# hanger0515.net
KiCad netlist of a schematic drawn in EasyEDA Pro
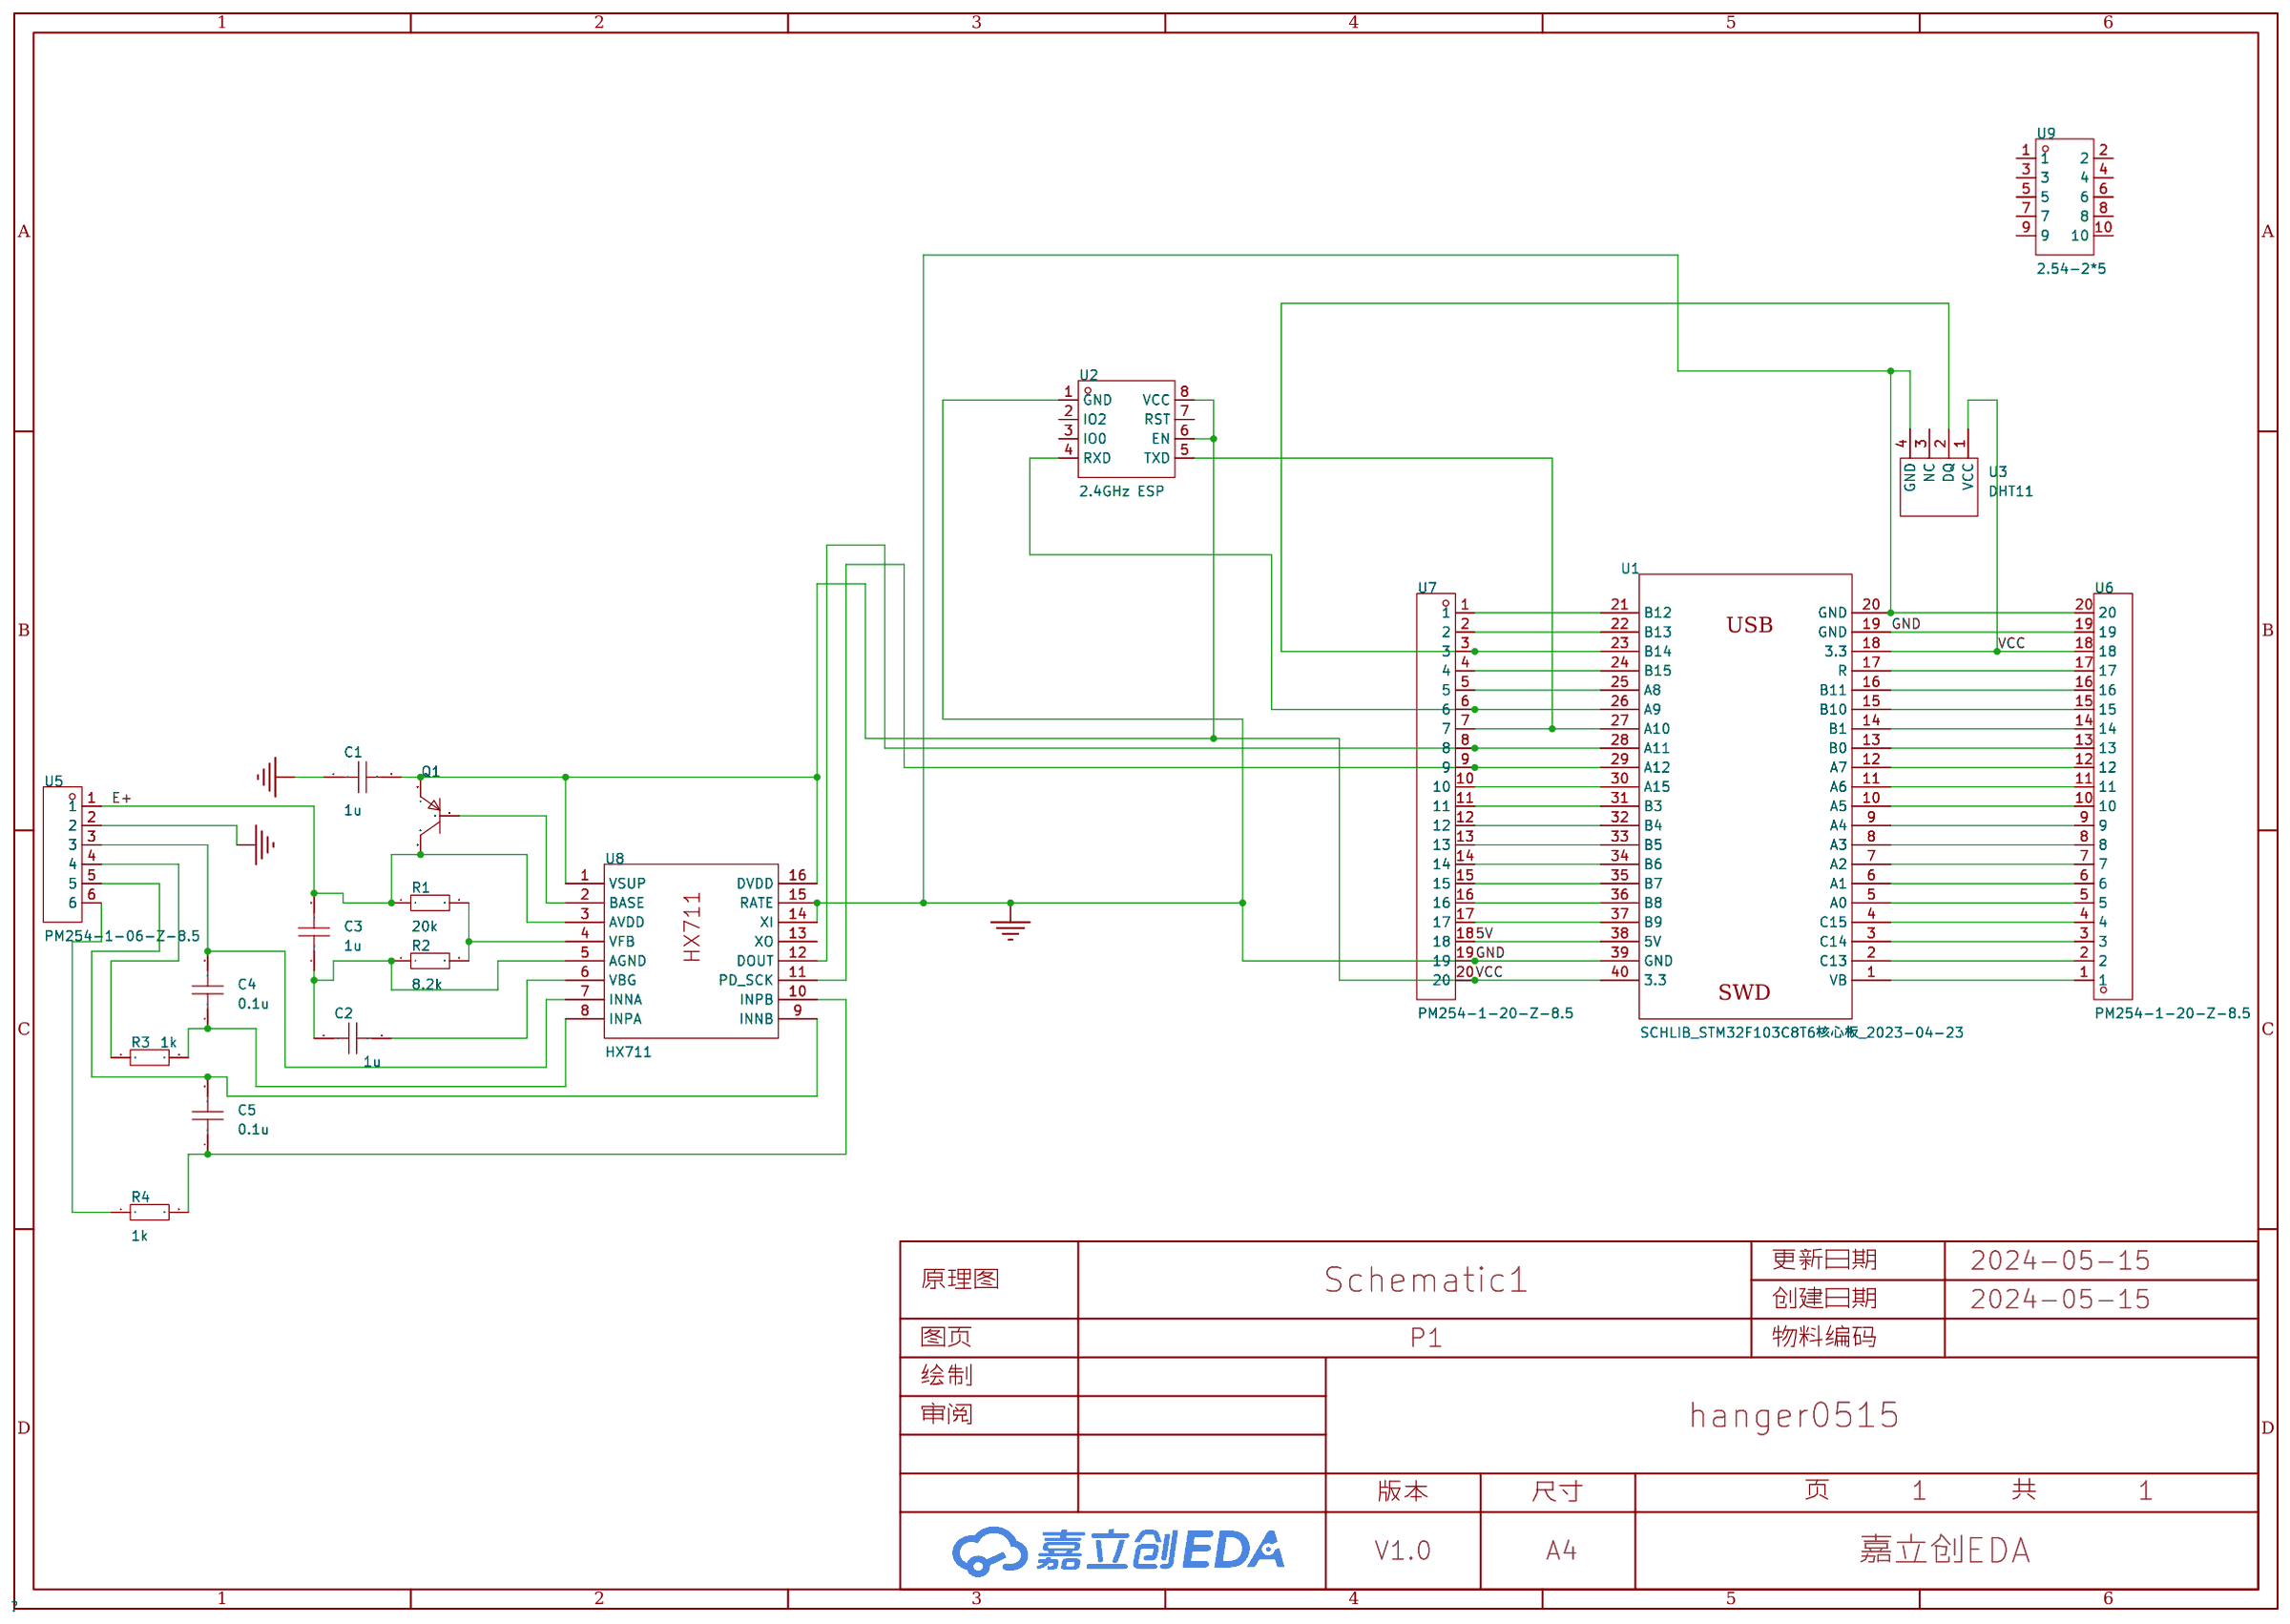
[diagram p0: schematic sheet]

(export (version "E")
  (design (tool "Eeschema 10.0.6"))
  (components
    (comp (ref "C1")
      (value "1u")
      (footprint "easyedapro:C0603")
      (libsource (lib "easyedapro") (part "CapAcitance"))
    )
    (comp (ref "C2")
      (value "1u")
      (footprint "easyedapro:C0603")
      (libsource (lib "easyedapro") (part "CapAcitance"))
    )
    (comp (ref "C3")
      (value "1u")
      (footprint "easyedapro:C0603")
      (libsource (lib "easyedapro") (part "CapAcitance"))
    )
    (comp (ref "C4")
      (value "0.1u")
      (footprint "easyedapro:C0603")
      (libsource (lib "easyedapro") (part "CapAcitance"))
    )
    (comp (ref "C5")
      (value "0.1u")
      (footprint "easyedapro:C0603")
      (libsource (lib "easyedapro") (part "CapAcitance"))
    )
    (comp (ref "Q1")
      (value "~")
      (footprint "easyedapro:S8550P_SOT")
      (libsource (lib "easyedapro") (part "PNP"))
    )
    (comp (ref "R1") (value "20k") (footprint "easyedapro:R0603") (libsource (lib "easyedapro") (part "电阻")))
    (comp (ref "R2") (value "8.2k") (footprint "easyedapro:R0603") (libsource (lib "easyedapro") (part "电阻")))
    (comp (ref "R3") (value "1k") (footprint "easyedapro:R0603") (libsource (lib "easyedapro") (part "电阻")))
    (comp (ref "R4") (value "1k") (footprint "easyedapro:R0603") (libsource (lib "easyedapro") (part "电阻")))
    (comp (ref "U1")
      (value "SCHLIB_STM32F103C8T6核心板_2023-04-23")
      (footprint "easyedapro:STM32F103C8T6核心板 STM32开发板ARM嵌入式单片机小系统实验板")
      (libsource (lib "easyedapro") (part "SCHLIB_STM32F103C8T6核心板_2023-04-23"))
    )
    (comp (ref "U2")
      (value "2.4GHz ESP")
      (footprint "easyedapro:WIFIM-TH_8P-L24.7-W14.4-P2.54")
      (description "核心处理器:-;频率:2.4GHz;天线形式:板载PCB天线;发射功率:16dBm;接收灵敏度:-90dBm;")
      (fields (field (name "Manufacturer Part") "ESP-01") (field (name "Manufacturer") "Ai-Thinker(安信可)"))
      (libsource (lib "easyedapro") (part "ESP-01"))
    )
    (comp (ref "U3")
      (value "DHT11")
      (footprint "easyedapro:DHT11")
      (libsource (lib "easyedapro") (part "DHT11"))
    )
    (comp (ref "U5")
      (value "PM254-1-06-Z-8.5")
      (footprint "easyedapro:HDR-TH_6P-P2.54-V-F")
      (fields (field (name "Manufacturer") "HCTL(华灿天禄)"))
      (libsource (lib "easyedapro") (part "PM254-1-06-Z-8.5"))
    )
    (comp (ref "U6")
      (value "PM254-1-20-Z-8.5")
      (footprint "easyedapro:HDR-TH_20P-P2.54-V-F-2")
      (fields (field (name "Manufacturer") "HCTL(华灿天禄)"))
      (libsource (lib "easyedapro") (part "PM254-1-20-Z-8.5"))
    )
    (comp (ref "U7")
      (value "PM254-1-20-Z-8.5")
      (footprint "easyedapro:HDR-TH_20P-P2.54-V-F-2")
      (fields (field (name "Manufacturer") "HCTL(华灿天禄)"))
      (libsource (lib "easyedapro") (part "PM254-1-20-Z-8.5"))
    )
    (comp (ref "U8")
      (value "HX711")
      (footprint "easyedapro:SOP-16_L10.0-W3.9-P1.27-LS6.0-BL")
      (description "称重AD采集芯片")
      (fields (field (name "Manufacturer") "AVIA(海芯科技)"))
      (libsource (lib "easyedapro") (part "HX711"))
    )
    (comp (ref "U9")
      (value "2.54-2*5")
      (footprint "easyedapro:HDR-TH_10P-P2.54-V-F-R2-C5-S2.54")
      (fields (field (name "Manufacturer") "ZHOURI(洲日)"))
      (libsource (lib "easyedapro") (part "2.54-2*5"))
    )
  )
  (nets
    (net (code "1") (name "/5V") (class "Default")
      (node (ref "U1") (pin "38") (pinfunction "5V_38") (pintype "input"))
      (node (ref "U7") (pin "18") (pinfunction "18_18") (pintype "unspecified"))
    )
    (net (code "2") (name "/E+") (class "Default")
      (node (ref "C3") (pin "2") (pinfunction "2_2") (pintype "input"))
      (node (ref "Q1") (pin "3") (pinfunction "C_3") (pintype "input"))
      (node (ref "R1") (pin "1") (pinfunction "1_1") (pintype "input"))
      (node (ref "U5") (pin "1") (pinfunction "1_1") (pintype "unspecified"))
      (node (ref "U8") (pin "3") (pinfunction "AVDD_3") (pintype "unspecified"))
    )
    (net (code "3") (name "/VCC") (class "Default")
      (node (ref "C1") (pin "2") (pinfunction "2_2") (pintype "input"))
      (node (ref "Q1") (pin "2") (pinfunction "E_2") (pintype "input"))
      (node (ref "U1") (pin "18") (pinfunction "3.3_18") (pintype "input"))
      (node (ref "U1") (pin "40") (pinfunction "3.3_40") (pintype "input"))
      (node (ref "U2") (pin "6") (pinfunction "EN_6") (pintype "input"))
      (node (ref "U2") (pin "8") (pinfunction "VCC_8") (pintype "input"))
      (node (ref "U3") (pin "1") (pinfunction "VCC_1") (pintype "input"))
      (node (ref "U6") (pin "18") (pinfunction "18_18") (pintype "unspecified"))
      (node (ref "U7") (pin "20") (pinfunction "20_20") (pintype "unspecified"))
      (node (ref "U8") (pin "1") (pinfunction "VSUP_1") (pintype "unspecified"))
      (node (ref "U8") (pin "16") (pinfunction "DVDD_16") (pintype "unspecified"))
    )
    (net (code "4") (name "GND") (class "Default")
      (node (ref "C1") (pin "1") (pinfunction "1_1") (pintype "input"))
      (node (ref "U1") (pin "19") (pinfunction "GND_19") (pintype "input"))
      (node (ref "U1") (pin "20") (pinfunction "GND_20") (pintype "input"))
      (node (ref "U1") (pin "39") (pinfunction "GND_39") (pintype "input"))
      (node (ref "U2") (pin "1") (pinfunction "GND_1") (pintype "input"))
      (node (ref "U3") (pin "4") (pinfunction "GND_4") (pintype "input"))
      (node (ref "U5") (pin "2") (pinfunction "2_2") (pintype "unspecified"))
      (node (ref "U6") (pin "19") (pinfunction "19_19") (pintype "unspecified"))
      (node (ref "U6") (pin "20") (pinfunction "20_20") (pintype "unspecified"))
      (node (ref "U7") (pin "19") (pinfunction "19_19") (pintype "unspecified"))
      (node (ref "U8") (pin "14") (pinfunction "XI_14") (pintype "unspecified"))
      (node (ref "U8") (pin "15") (pinfunction "RATE_15") (pintype "unspecified"))
    )
    (net (code "5") (name "Net-(Q1-B)") (class "Default")
      (node (ref "Q1") (pin "1") (pinfunction "B_1") (pintype "input"))
      (node (ref "U8") (pin "2") (pinfunction "BASE_2") (pintype "unspecified"))
    )
    (net (code "6") (name "Net-(R3-Pad1)") (class "Default")
      (node (ref "R3") (pin "1") (pinfunction "1_1") (pintype "input"))
      (node (ref "U5") (pin "4") (pinfunction "4_4") (pintype "unspecified"))
    )
    (net (code "7") (name "Net-(R4-Pad1)") (class "Default")
      (node (ref "R4") (pin "1") (pinfunction "1_1") (pintype "input"))
      (node (ref "U5") (pin "6") (pinfunction "6_6") (pintype "unspecified"))
    )
    (net (code "8") (name "Net-(U1-A0)") (class "Default")
      (node (ref "U1") (pin "5") (pinfunction "A0_5") (pintype "input"))
      (node (ref "U6") (pin "5") (pinfunction "5_5") (pintype "unspecified"))
    )
    (net (code "9") (name "Net-(U1-A1)") (class "Default")
      (node (ref "U1") (pin "6") (pinfunction "A1_6") (pintype "input"))
      (node (ref "U6") (pin "6") (pinfunction "6_6") (pintype "unspecified"))
    )
    (net (code "10") (name "Net-(U1-A2)") (class "Default")
      (node (ref "U1") (pin "7") (pinfunction "A2_7") (pintype "input"))
      (node (ref "U6") (pin "7") (pinfunction "7_7") (pintype "unspecified"))
    )
    (net (code "11") (name "Net-(U1-A3)") (class "Default")
      (node (ref "U1") (pin "8") (pinfunction "A3_8") (pintype "input"))
      (node (ref "U6") (pin "8") (pinfunction "8_8") (pintype "unspecified"))
    )
    (net (code "12") (name "Net-(U1-A4)") (class "Default")
      (node (ref "U1") (pin "9") (pinfunction "A4_9") (pintype "input"))
      (node (ref "U6") (pin "9") (pinfunction "9_9") (pintype "unspecified"))
    )
    (net (code "13") (name "Net-(U1-A5)") (class "Default")
      (node (ref "U1") (pin "10") (pinfunction "A5_10") (pintype "input"))
      (node (ref "U6") (pin "10") (pinfunction "10_10") (pintype "unspecified"))
    )
    (net (code "14") (name "Net-(U1-A6)") (class "Default")
      (node (ref "U1") (pin "11") (pinfunction "A6_11") (pintype "input"))
      (node (ref "U6") (pin "11") (pinfunction "11_11") (pintype "unspecified"))
    )
    (net (code "15") (name "Net-(U1-A7)") (class "Default")
      (node (ref "U1") (pin "12") (pinfunction "A7_12") (pintype "input"))
      (node (ref "U6") (pin "12") (pinfunction "12_12") (pintype "unspecified"))
    )
    (net (code "16") (name "Net-(U1-A8)") (class "Default")
      (node (ref "U1") (pin "25") (pinfunction "A8_25") (pintype "input"))
      (node (ref "U7") (pin "5") (pinfunction "5_5") (pintype "unspecified"))
    )
    (net (code "17") (name "Net-(U1-A9)") (class "Default")
      (node (ref "U1") (pin "26") (pinfunction "A9_26") (pintype "input"))
      (node (ref "U2") (pin "4") (pinfunction "RXD_4") (pintype "input"))
      (node (ref "U7") (pin "6") (pinfunction "6_6") (pintype "unspecified"))
    )
    (net (code "18") (name "Net-(U1-A10)") (class "Default")
      (node (ref "U1") (pin "27") (pinfunction "A10_27") (pintype "input"))
      (node (ref "U2") (pin "5") (pinfunction "TXD_5") (pintype "input"))
      (node (ref "U7") (pin "7") (pinfunction "7_7") (pintype "unspecified"))
    )
    (net (code "19") (name "Net-(U1-A11)") (class "Default")
      (node (ref "U1") (pin "28") (pinfunction "A11_28") (pintype "input"))
      (node (ref "U7") (pin "8") (pinfunction "8_8") (pintype "unspecified"))
      (node (ref "U8") (pin "12") (pinfunction "DOUT_12") (pintype "unspecified"))
    )
    (net (code "20") (name "Net-(U1-A12)") (class "Default")
      (node (ref "U1") (pin "29") (pinfunction "A12_29") (pintype "input"))
      (node (ref "U7") (pin "9") (pinfunction "9_9") (pintype "unspecified"))
      (node (ref "U8") (pin "11") (pinfunction "PD_SCK_11") (pintype "unspecified"))
    )
    (net (code "21") (name "Net-(U1-A15)") (class "Default")
      (node (ref "U1") (pin "30") (pinfunction "A15_30") (pintype "input"))
      (node (ref "U7") (pin "10") (pinfunction "10_10") (pintype "unspecified"))
    )
    (net (code "22") (name "Net-(U1-B0)") (class "Default")
      (node (ref "U1") (pin "13") (pinfunction "B0_13") (pintype "input"))
      (node (ref "U6") (pin "13") (pinfunction "13_13") (pintype "unspecified"))
    )
    (net (code "23") (name "Net-(U1-B1)") (class "Default")
      (node (ref "U1") (pin "14") (pinfunction "B1_14") (pintype "input"))
      (node (ref "U6") (pin "14") (pinfunction "14_14") (pintype "unspecified"))
    )
    (net (code "24") (name "Net-(U1-B3)") (class "Default")
      (node (ref "U1") (pin "31") (pinfunction "B3_31") (pintype "input"))
      (node (ref "U7") (pin "11") (pinfunction "11_11") (pintype "unspecified"))
    )
    (net (code "25") (name "Net-(U1-B4)") (class "Default")
      (node (ref "U1") (pin "32") (pinfunction "B4_32") (pintype "input"))
      (node (ref "U7") (pin "12") (pinfunction "12_12") (pintype "unspecified"))
    )
    (net (code "26") (name "Net-(U1-B5)") (class "Default")
      (node (ref "U1") (pin "33") (pinfunction "B5_33") (pintype "input"))
      (node (ref "U7") (pin "13") (pinfunction "13_13") (pintype "unspecified"))
    )
    (net (code "27") (name "Net-(U1-B6)") (class "Default")
      (node (ref "U1") (pin "34") (pinfunction "B6_34") (pintype "input"))
      (node (ref "U7") (pin "14") (pinfunction "14_14") (pintype "unspecified"))
    )
    (net (code "28") (name "Net-(U1-B7)") (class "Default")
      (node (ref "U1") (pin "35") (pinfunction "B7_35") (pintype "input"))
      (node (ref "U7") (pin "15") (pinfunction "15_15") (pintype "unspecified"))
    )
    (net (code "29") (name "Net-(U1-B8)") (class "Default")
      (node (ref "U1") (pin "36") (pinfunction "B8_36") (pintype "input"))
      (node (ref "U7") (pin "16") (pinfunction "16_16") (pintype "unspecified"))
    )
    (net (code "30") (name "Net-(U1-B9)") (class "Default")
      (node (ref "U1") (pin "37") (pinfunction "B9_37") (pintype "input"))
      (node (ref "U7") (pin "17") (pinfunction "17_17") (pintype "unspecified"))
    )
    (net (code "31") (name "Net-(U1-B10)") (class "Default")
      (node (ref "U1") (pin "15") (pinfunction "B10_15") (pintype "input"))
      (node (ref "U6") (pin "15") (pinfunction "15_15") (pintype "unspecified"))
    )
    (net (code "32") (name "Net-(U1-B11)") (class "Default")
      (node (ref "U1") (pin "16") (pinfunction "B11_16") (pintype "input"))
      (node (ref "U6") (pin "16") (pinfunction "16_16") (pintype "unspecified"))
    )
    (net (code "33") (name "Net-(U1-B12)") (class "Default")
      (node (ref "U1") (pin "21") (pinfunction "B12_21") (pintype "input"))
      (node (ref "U7") (pin "1") (pinfunction "1_1") (pintype "unspecified"))
    )
    (net (code "34") (name "Net-(U1-B13)") (class "Default")
      (node (ref "U1") (pin "22") (pinfunction "B13_22") (pintype "input"))
      (node (ref "U7") (pin "2") (pinfunction "2_2") (pintype "unspecified"))
    )
    (net (code "35") (name "Net-(U1-B14)") (class "Default")
      (node (ref "U1") (pin "23") (pinfunction "B14_23") (pintype "input"))
      (node (ref "U3") (pin "2") (pinfunction "DQ_2") (pintype "input"))
      (node (ref "U7") (pin "3") (pinfunction "3_3") (pintype "unspecified"))
    )
    (net (code "36") (name "Net-(U1-B15)") (class "Default")
      (node (ref "U1") (pin "24") (pinfunction "B15_24") (pintype "input"))
      (node (ref "U7") (pin "4") (pinfunction "4_4") (pintype "unspecified"))
    )
    (net (code "37") (name "Net-(U1-C13)") (class "Default")
      (node (ref "U1") (pin "2") (pinfunction "C13_2") (pintype "input"))
      (node (ref "U6") (pin "2") (pinfunction "2_2") (pintype "unspecified"))
    )
    (net (code "38") (name "Net-(U1-C14)") (class "Default")
      (node (ref "U1") (pin "3") (pinfunction "C14_3") (pintype "input"))
      (node (ref "U6") (pin "3") (pinfunction "3_3") (pintype "unspecified"))
    )
    (net (code "39") (name "Net-(U1-C15)") (class "Default")
      (node (ref "U1") (pin "4") (pinfunction "C15_4") (pintype "input"))
      (node (ref "U6") (pin "4") (pinfunction "4_4") (pintype "unspecified"))
    )
    (net (code "40") (name "Net-(U1-R)") (class "Default")
      (node (ref "U1") (pin "17") (pinfunction "R_17") (pintype "input"))
      (node (ref "U6") (pin "17") (pinfunction "17_17") (pintype "unspecified"))
    )
    (net (code "41") (name "Net-(U1-VB)") (class "Default")
      (node (ref "U1") (pin "1") (pinfunction "VB_1") (pintype "input"))
      (node (ref "U6") (pin "1") (pinfunction "1_1") (pintype "unspecified"))
    )
    (net (code "42") (name "Net-(U8-AGND)") (class "Default")
      (node (ref "C2") (pin "1") (pinfunction "1_1") (pintype "input"))
      (node (ref "C3") (pin "1") (pinfunction "1_1") (pintype "input"))
      (node (ref "R2") (pin "1") (pinfunction "1_1") (pintype "input"))
      (node (ref "U8") (pin "5") (pinfunction "AGND_5") (pintype "unspecified"))
    )
    (net (code "43") (name "Net-(U8-INNA)") (class "Default")
      (node (ref "C4") (pin "2") (pinfunction "2_2") (pintype "input"))
      (node (ref "U5") (pin "3") (pinfunction "3_3") (pintype "unspecified"))
      (node (ref "U8") (pin "7") (pinfunction "INNA_7") (pintype "unspecified"))
    )
    (net (code "44") (name "Net-(U8-INNB)") (class "Default")
      (node (ref "C5") (pin "2") (pinfunction "2_2") (pintype "input"))
      (node (ref "U5") (pin "5") (pinfunction "5_5") (pintype "unspecified"))
      (node (ref "U8") (pin "9") (pinfunction "INNB_9") (pintype "unspecified"))
    )
    (net (code "45") (name "Net-(U8-INPA)") (class "Default")
      (node (ref "C4") (pin "1") (pinfunction "1_1") (pintype "input"))
      (node (ref "R3") (pin "2") (pinfunction "2_2") (pintype "input"))
      (node (ref "U8") (pin "8") (pinfunction "INPA_8") (pintype "unspecified"))
    )
    (net (code "46") (name "Net-(U8-INPB)") (class "Default")
      (node (ref "C5") (pin "1") (pinfunction "1_1") (pintype "input"))
      (node (ref "R4") (pin "2") (pinfunction "2_2") (pintype "input"))
      (node (ref "U8") (pin "10") (pinfunction "INPB_10") (pintype "unspecified"))
    )
    (net (code "47") (name "Net-(U8-VBG)") (class "Default")
      (node (ref "C2") (pin "2") (pinfunction "2_2") (pintype "input"))
      (node (ref "U8") (pin "6") (pinfunction "VBG_6") (pintype "unspecified"))
    )
    (net (code "48") (name "Net-(U8-VFB)") (class "Default")
      (node (ref "R1") (pin "2") (pinfunction "2_2") (pintype "input"))
      (node (ref "R2") (pin "2") (pinfunction "2_2") (pintype "input"))
      (node (ref "U8") (pin "4") (pinfunction "VFB_4") (pintype "unspecified"))
    )
    (net (code "49") (name "unconnected-(U2-IO0-Pad3)") (class "Default")
      (node (ref "U2") (pin "3") (pinfunction "IO0_3") (pintype "input"))
    )
    (net (code "50") (name "unconnected-(U2-IO2-Pad2)") (class "Default")
      (node (ref "U2") (pin "2") (pinfunction "IO2_2") (pintype "input"))
    )
    (net (code "51") (name "unconnected-(U2-RST-Pad7)") (class "Default")
      (node (ref "U2") (pin "7") (pinfunction "RST_7") (pintype "input"))
    )
    (net (code "52") (name "unconnected-(U3-NC-Pad3)") (class "Default")
      (node (ref "U3") (pin "3") (pinfunction "NC_3") (pintype "input"))
    )
    (net (code "53") (name "unconnected-(U8-XO-Pad13)") (class "Default")
      (node (ref "U8") (pin "13") (pinfunction "XO_13") (pintype "unspecified"))
    )
    (net (code "54") (name "unconnected-(U9-Pad1)") (class "Default")
      (node (ref "U9") (pin "1") (pinfunction "1_1") (pintype "unspecified"))
    )
    (net (code "55") (name "unconnected-(U9-Pad2)") (class "Default")
      (node (ref "U9") (pin "2") (pinfunction "2_2") (pintype "unspecified"))
    )
    (net (code "56") (name "unconnected-(U9-Pad3)") (class "Default")
      (node (ref "U9") (pin "3") (pinfunction "3_3") (pintype "unspecified"))
    )
    (net (code "57") (name "unconnected-(U9-Pad4)") (class "Default")
      (node (ref "U9") (pin "4") (pinfunction "4_4") (pintype "unspecified"))
    )
    (net (code "58") (name "unconnected-(U9-Pad5)") (class "Default")
      (node (ref "U9") (pin "5") (pinfunction "5_5") (pintype "unspecified"))
    )
    (net (code "59") (name "unconnected-(U9-Pad6)") (class "Default")
      (node (ref "U9") (pin "6") (pinfunction "6_6") (pintype "unspecified"))
    )
    (net (code "60") (name "unconnected-(U9-Pad7)") (class "Default")
      (node (ref "U9") (pin "7") (pinfunction "7_7") (pintype "unspecified"))
    )
    (net (code "61") (name "unconnected-(U9-Pad8)") (class "Default")
      (node (ref "U9") (pin "8") (pinfunction "8_8") (pintype "unspecified"))
    )
    (net (code "62") (name "unconnected-(U9-Pad9)") (class "Default")
      (node (ref "U9") (pin "9") (pinfunction "9_9") (pintype "unspecified"))
    )
    (net (code "63") (name "unconnected-(U9-Pad10)") (class "Default")
      (node (ref "U9") (pin "10") (pinfunction "10_10") (pintype "unspecified"))
    )
  )
)
